# m80-v0_65.net
KiCad netlist of a schematic drawn in EAGLE
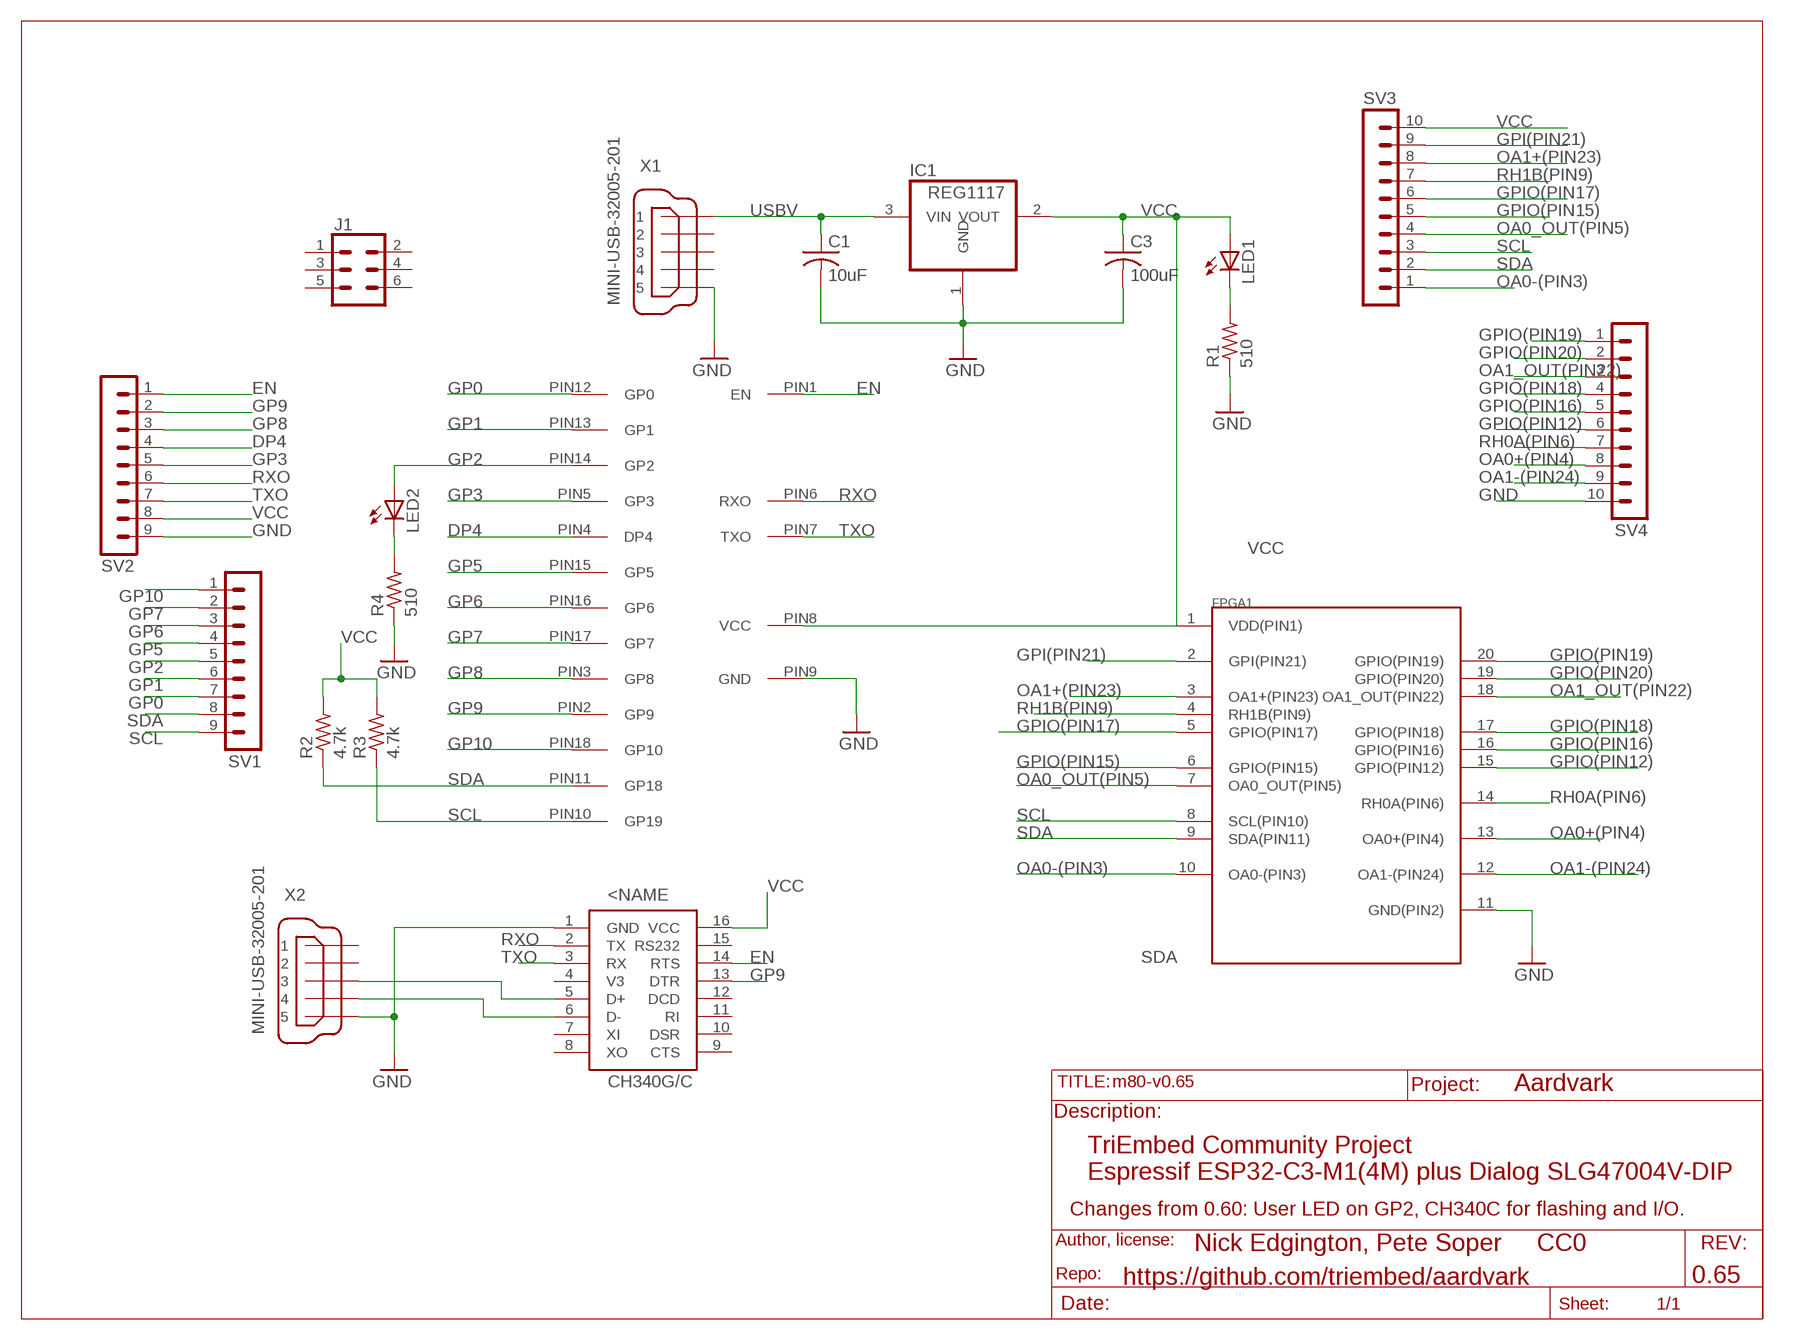
[diagram p0: schematic, sheet 1]

(export (version "E")
  (design (tool "Eeschema 10.0.6"))
  (components
    (comp (ref "C1")
      (value "10uF")
      (footprint "eagle-import:C0805")
      (libsource (lib "eagle-import") (part "C-USC0805"))
    )
    (comp (ref "C3")
      (value "100uF")
      (footprint "eagle-import:C1206")
      (libsource (lib "eagle-import") (part "C-USC1206"))
    )
    (comp (ref "FPGA1")
      (value "SLG7004V_DIP")
      (footprint "eagle-import:SLG47004V-DIP")
      (libsource (lib "eagle-import") (part "SLG7004V_DIP"))
    )
    (comp (ref "IC1")
      (value "REG1117")
      (footprint "eagle-import:SOT223")
      (libsource (lib "eagle-import") (part "REG1117"))
    )
    (comp (ref "IC2")
      (value "CH340G")
      (footprint "eagle-import:SOIC16")
      (libsource (lib "eagle-import") (part "CH340G"))
    )
    (comp (ref "J1")
      (value "CONN_03X2NO_SILK")
      (footprint "eagle-import:2X3-NS")
      (libsource (lib "eagle-import") (part "CONN_03X2NO_SILK"))
    )
    (comp (ref "LED1")
      (value "LEDCHIP-LED0805")
      (footprint "eagle-import:CHIP-LED0805")
      (libsource (lib "eagle-import") (part "LEDCHIP-LED0805"))
    )
    (comp (ref "LED2")
      (value "LEDCHIP-LED0805")
      (footprint "eagle-import:CHIP-LED0805")
      (libsource (lib "eagle-import") (part "LEDCHIP-LED0805"))
    )
    (comp (ref "R1")
      (value "510")
      (footprint "eagle-import:R0805")
      (libsource (lib "eagle-import") (part "R-US_R0805"))
    )
    (comp (ref "R2")
      (value "4.7k")
      (footprint "eagle-import:R0805")
      (libsource (lib "eagle-import") (part "R-US_R0805"))
    )
    (comp (ref "R3")
      (value "4.7k")
      (footprint "eagle-import:R0805")
      (libsource (lib "eagle-import") (part "R-US_R0805"))
    )
    (comp (ref "R4")
      (value "510")
      (footprint "eagle-import:R0805")
      (libsource (lib "eagle-import") (part "R-US_R0805"))
    )
    (comp (ref "SV1")
      (value "MA09-1")
      (footprint "eagle-import:MA09-1")
      (libsource (lib "eagle-import") (part "MA09-1"))
    )
    (comp (ref "SV2")
      (value "MA09-1")
      (footprint "eagle-import:MA09-1")
      (libsource (lib "eagle-import") (part "MA09-1"))
    )
    (comp (ref "SV3")
      (value "MA10-1")
      (footprint "eagle-import:MA10-1")
      (libsource (lib "eagle-import") (part "MA10-1"))
    )
    (comp (ref "SV4")
      (value "MA10-1")
      (footprint "eagle-import:MA10-1")
      (libsource (lib "eagle-import") (part "MA10-1"))
    )
    (comp (ref "U$2")
      (value "UNTITLED_ESP32C3")
      (footprint "eagle-import:UNTITLED_ESP32-C3-01M")
      (libsource (lib "eagle-import") (part "UNTITLED_ESP32C3"))
    )
    (comp (ref "X1")
      (value "MINI-USB-32005-201")
      (footprint "eagle-import:32005-201")
      (libsource (lib "eagle-import") (part "MINI-USB-32005-201"))
    )
    (comp (ref "X2")
      (value "MINI-USB-32005-201")
      (footprint "eagle-import:32005-201")
      (libsource (lib "eagle-import") (part "MINI-USB-32005-201"))
    )
  )
  (nets
    (net (code "1") (name "/DP4") (class "Default")
      (node (ref "SV2") (pin "4") (pinfunction "4_4") (pintype "passive"))
      (node (ref "U$2") (pin "PIN4") (pinfunction "DP4_PIN4") (pintype "bidirectional"))
    )
    (net (code "2") (name "/EN") (class "Default")
      (node (ref "IC2") (pin "14") (pinfunction "RTS_14") (pintype "bidirectional"))
      (node (ref "SV2") (pin "1") (pinfunction "1_1") (pintype "passive"))
      (node (ref "U$2") (pin "PIN1") (pinfunction "EN_PIN1") (pintype "input"))
    )
    (net (code "3") (name "/GP0") (class "Default")
      (node (ref "SV1") (pin "7") (pinfunction "7_7") (pintype "passive"))
      (node (ref "U$2") (pin "PIN12") (pinfunction "GP0_PIN12") (pintype "bidirectional"))
    )
    (net (code "4") (name "/GP1") (class "Default")
      (node (ref "SV1") (pin "6") (pinfunction "6_6") (pintype "passive"))
      (node (ref "U$2") (pin "PIN13") (pinfunction "GP1_PIN13") (pintype "bidirectional"))
    )
    (net (code "5") (name "/GP2") (class "Default")
      (node (ref "LED2") (pin "A") (pinfunction "A_A") (pintype "passive"))
      (node (ref "SV1") (pin "5") (pinfunction "5_5") (pintype "passive"))
      (node (ref "U$2") (pin "PIN14") (pinfunction "GP2_PIN14") (pintype "bidirectional"))
    )
    (net (code "6") (name "/GP3") (class "Default")
      (node (ref "SV2") (pin "5") (pinfunction "5_5") (pintype "passive"))
      (node (ref "U$2") (pin "PIN5") (pinfunction "GP3_PIN5") (pintype "bidirectional"))
    )
    (net (code "7") (name "/GP5") (class "Default")
      (node (ref "SV1") (pin "4") (pinfunction "4_4") (pintype "passive"))
      (node (ref "U$2") (pin "PIN15") (pinfunction "GP5_PIN15") (pintype "bidirectional"))
    )
    (net (code "8") (name "/GP6") (class "Default")
      (node (ref "SV1") (pin "3") (pinfunction "3_3") (pintype "passive"))
      (node (ref "U$2") (pin "PIN16") (pinfunction "GP6_PIN16") (pintype "bidirectional"))
    )
    (net (code "9") (name "/GP7") (class "Default")
      (node (ref "SV1") (pin "2") (pinfunction "2_2") (pintype "passive"))
      (node (ref "U$2") (pin "PIN17") (pinfunction "GP7_PIN17") (pintype "bidirectional"))
    )
    (net (code "10") (name "/GP8") (class "Default")
      (node (ref "SV2") (pin "3") (pinfunction "3_3") (pintype "passive"))
      (node (ref "U$2") (pin "PIN3") (pinfunction "GP8_PIN3") (pintype "bidirectional"))
    )
    (net (code "11") (name "/GP9") (class "Default")
      (node (ref "IC2") (pin "13") (pinfunction "DTR_13") (pintype "bidirectional"))
      (node (ref "SV2") (pin "2") (pinfunction "2_2") (pintype "passive"))
      (node (ref "U$2") (pin "PIN2") (pinfunction "GP9_PIN2") (pintype "bidirectional"))
    )
    (net (code "12") (name "/GP10") (class "Default")
      (node (ref "SV1") (pin "1") (pinfunction "1_1") (pintype "passive"))
      (node (ref "U$2") (pin "PIN18") (pinfunction "GP10_PIN18") (pintype "bidirectional"))
    )
    (net (code "13") (name "/GPI(PIN21)") (class "Default")
      (node (ref "FPGA1") (pin "2") (pinfunction "GPI(PIN21)_2") (pintype "input"))
      (node (ref "SV3") (pin "9") (pinfunction "9_9") (pintype "passive"))
    )
    (net (code "14") (name "/GPIO(PIN12)") (class "Default")
      (node (ref "FPGA1") (pin "15") (pinfunction "GPIO(PIN12)_15") (pintype "bidirectional"))
      (node (ref "SV4") (pin "6") (pinfunction "6_6") (pintype "passive"))
    )
    (net (code "15") (name "/GPIO(PIN15)") (class "Default")
      (node (ref "FPGA1") (pin "6") (pinfunction "GPIO(PIN15)_6") (pintype "bidirectional"))
      (node (ref "SV3") (pin "5") (pinfunction "5_5") (pintype "passive"))
    )
    (net (code "16") (name "/GPIO(PIN16)") (class "Default")
      (node (ref "FPGA1") (pin "16") (pinfunction "GPIO(PIN16)_16") (pintype "bidirectional"))
      (node (ref "SV4") (pin "5") (pinfunction "5_5") (pintype "passive"))
    )
    (net (code "17") (name "/GPIO(PIN17)") (class "Default")
      (node (ref "FPGA1") (pin "5") (pinfunction "GPIO(PIN17)_5") (pintype "bidirectional"))
      (node (ref "SV3") (pin "6") (pinfunction "6_6") (pintype "passive"))
    )
    (net (code "18") (name "/GPIO(PIN18)") (class "Default")
      (node (ref "FPGA1") (pin "17") (pinfunction "GPIO(PIN18)_17") (pintype "input"))
      (node (ref "SV4") (pin "4") (pinfunction "4_4") (pintype "passive"))
    )
    (net (code "19") (name "/GPIO(PIN19)") (class "Default")
      (node (ref "FPGA1") (pin "20") (pinfunction "GPIO(PIN19)_20") (pintype "bidirectional"))
      (node (ref "SV4") (pin "1") (pinfunction "1_1") (pintype "passive"))
    )
    (net (code "20") (name "/GPIO(PIN20)") (class "Default")
      (node (ref "FPGA1") (pin "19") (pinfunction "GPIO(PIN20)_19") (pintype "bidirectional"))
      (node (ref "SV4") (pin "2") (pinfunction "2_2") (pintype "passive"))
    )
    (net (code "21") (name "/OA0+(PIN4)") (class "Default")
      (node (ref "FPGA1") (pin "13") (pinfunction "OA0+(PIN4)_13") (pintype "bidirectional"))
      (node (ref "SV4") (pin "8") (pinfunction "8_8") (pintype "passive"))
    )
    (net (code "22") (name "/OA0-(PIN3)") (class "Default")
      (node (ref "FPGA1") (pin "10") (pinfunction "OA0-(PIN3)_10") (pintype "open_collector"))
      (node (ref "SV3") (pin "1") (pinfunction "1_1") (pintype "passive"))
    )
    (net (code "23") (name "/OA0_OUT(PIN5)") (class "Default")
      (node (ref "FPGA1") (pin "7") (pinfunction "OA0_OUT(PIN5)_7") (pintype "bidirectional"))
      (node (ref "SV3") (pin "4") (pinfunction "4_4") (pintype "passive"))
    )
    (net (code "24") (name "/OA1+(PIN23)") (class "Default")
      (node (ref "FPGA1") (pin "3") (pinfunction "OA1+(PIN23)_3") (pintype "bidirectional"))
      (node (ref "SV3") (pin "8") (pinfunction "8_8") (pintype "passive"))
    )
    (net (code "25") (name "/OA1-(PIN24)") (class "Default")
      (node (ref "FPGA1") (pin "12") (pinfunction "OA1-(PIN24)_12") (pintype "bidirectional"))
      (node (ref "SV4") (pin "9") (pinfunction "9_9") (pintype "passive"))
    )
    (net (code "26") (name "/OA1_OUT(PIN22)") (class "Default")
      (node (ref "FPGA1") (pin "18") (pinfunction "OA1_OUT(PIN22)_18") (pintype "bidirectional"))
      (node (ref "SV4") (pin "3") (pinfunction "3_3") (pintype "passive"))
    )
    (net (code "27") (name "/RH0A(PIN6)") (class "Default")
      (node (ref "FPGA1") (pin "14") (pinfunction "RH0A(PIN6)_14") (pintype "passive"))
      (node (ref "SV4") (pin "7") (pinfunction "7_7") (pintype "passive"))
    )
    (net (code "28") (name "/RH1B(PIN9)") (class "Default")
      (node (ref "FPGA1") (pin "4") (pinfunction "RH1B(PIN9)_4") (pintype "passive"))
      (node (ref "SV3") (pin "7") (pinfunction "7_7") (pintype "passive"))
    )
    (net (code "29") (name "/RXO") (class "Default")
      (node (ref "IC2") (pin "2") (pinfunction "TX_2") (pintype "bidirectional"))
      (node (ref "SV2") (pin "6") (pinfunction "6_6") (pintype "passive"))
      (node (ref "U$2") (pin "PIN6") (pinfunction "RXO_PIN6") (pintype "bidirectional"))
    )
    (net (code "30") (name "/SCL") (class "Default")
      (node (ref "FPGA1") (pin "8") (pinfunction "SCL(PIN10)_8") (pintype "bidirectional"))
      (node (ref "R3") (pin "1") (pinfunction "1_1") (pintype "passive"))
      (node (ref "SV1") (pin "9") (pinfunction "9_9") (pintype "passive"))
      (node (ref "SV3") (pin "3") (pinfunction "3_3") (pintype "passive"))
      (node (ref "U$2") (pin "PIN10") (pinfunction "GP19_PIN10") (pintype "bidirectional"))
    )
    (net (code "31") (name "/SDA") (class "Default")
      (node (ref "FPGA1") (pin "9") (pinfunction "SDA(PIN11)_9") (pintype "bidirectional"))
      (node (ref "R2") (pin "1") (pinfunction "1_1") (pintype "passive"))
      (node (ref "SV1") (pin "8") (pinfunction "8_8") (pintype "passive"))
      (node (ref "SV3") (pin "2") (pinfunction "2_2") (pintype "passive"))
      (node (ref "U$2") (pin "PIN11") (pinfunction "GP18_PIN11") (pintype "bidirectional"))
    )
    (net (code "32") (name "/TXO") (class "Default")
      (node (ref "IC2") (pin "3") (pinfunction "RX_3") (pintype "bidirectional"))
      (node (ref "SV2") (pin "7") (pinfunction "7_7") (pintype "passive"))
      (node (ref "U$2") (pin "PIN7") (pinfunction "TXO_PIN7") (pintype "bidirectional"))
    )
    (net (code "33") (name "/USBV") (class "Default")
      (node (ref "C1") (pin "1") (pinfunction "1_1") (pintype "passive"))
      (node (ref "IC1") (pin "3") (pinfunction "VIN_3") (pintype "input"))
      (node (ref "X1") (pin "1") (pinfunction "1_1") (pintype "passive"))
    )
    (net (code "34") (name "/VCC") (class "Default")
      (node (ref "C3") (pin "1") (pinfunction "1_1") (pintype "passive"))
      (node (ref "FPGA1") (pin "1") (pinfunction "VDD(PIN1)_1") (pintype "power_in"))
      (node (ref "IC1") (pin "2") (pinfunction "VOUT_2") (pintype "output"))
      (node (ref "IC2") (pin "16") (pinfunction "VCC_16") (pintype "power_in"))
      (node (ref "LED1") (pin "A") (pinfunction "A_A") (pintype "passive"))
      (node (ref "R2") (pin "2") (pinfunction "2_2") (pintype "passive"))
      (node (ref "R3") (pin "2") (pinfunction "2_2") (pintype "passive"))
      (node (ref "SV2") (pin "8") (pinfunction "8_8") (pintype "passive"))
      (node (ref "SV3") (pin "10") (pinfunction "10_10") (pintype "passive"))
      (node (ref "U$2") (pin "PIN8") (pinfunction "VCC_PIN8") (pintype "power_in"))
    )
    (net (code "35") (name "GND") (class "Default")
      (node (ref "C1") (pin "2") (pinfunction "2_2") (pintype "passive"))
      (node (ref "C3") (pin "2") (pinfunction "2_2") (pintype "passive"))
      (node (ref "FPGA1") (pin "11") (pinfunction "GND(PIN2)_11") (pintype "power_in"))
      (node (ref "IC1") (pin "1") (pinfunction "GND_1") (pintype "power_in"))
      (node (ref "IC2") (pin "1") (pinfunction "GND_1") (pintype "power_in"))
      (node (ref "R1") (pin "1") (pinfunction "1_1") (pintype "passive"))
      (node (ref "R4") (pin "1") (pinfunction "1_1") (pintype "passive"))
      (node (ref "SV2") (pin "9") (pinfunction "9_9") (pintype "passive"))
      (node (ref "SV4") (pin "10") (pinfunction "10_10") (pintype "passive"))
      (node (ref "U$2") (pin "PIN9") (pinfunction "GND_PIN9") (pintype "power_in"))
      (node (ref "X1") (pin "5") (pinfunction "5_5") (pintype "passive"))
      (node (ref "X2") (pin "5") (pinfunction "5_5") (pintype "passive"))
    )
    (net (code "36") (name "Net-(IC2-D+)") (class "Default")
      (node (ref "IC2") (pin "5") (pinfunction "D+_5") (pintype "bidirectional"))
      (node (ref "X2") (pin "3") (pinfunction "3_3") (pintype "passive"))
    )
    (net (code "37") (name "Net-(IC2-D-)") (class "Default")
      (node (ref "IC2") (pin "6") (pinfunction "D-_6") (pintype "bidirectional"))
      (node (ref "X2") (pin "4") (pinfunction "4_4") (pintype "passive"))
    )
    (net (code "38") (name "Net-(LED1-PadC)") (class "Default")
      (node (ref "LED1") (pin "C") (pinfunction "C_C") (pintype "passive"))
      (node (ref "R1") (pin "2") (pinfunction "2_2") (pintype "passive"))
    )
    (net (code "39") (name "Net-(LED2-PadC)") (class "Default")
      (node (ref "LED2") (pin "C") (pinfunction "C_C") (pintype "passive"))
      (node (ref "R4") (pin "2") (pinfunction "2_2") (pintype "passive"))
    )
    (net (code "40") (name "unconnected-(IC2-CTS-Pad9)") (class "Default")
      (node (ref "IC2") (pin "9") (pinfunction "CTS_9") (pintype "bidirectional"))
    )
    (net (code "41") (name "unconnected-(IC2-DCD-Pad12)") (class "Default")
      (node (ref "IC2") (pin "12") (pinfunction "DCD_12") (pintype "bidirectional"))
    )
    (net (code "42") (name "unconnected-(IC2-DSR-Pad10)") (class "Default")
      (node (ref "IC2") (pin "10") (pinfunction "DSR_10") (pintype "bidirectional"))
    )
    (net (code "43") (name "unconnected-(IC2-RI-Pad11)") (class "Default")
      (node (ref "IC2") (pin "11") (pinfunction "RI_11") (pintype "bidirectional"))
    )
    (net (code "44") (name "unconnected-(IC2-RS232-Pad15)") (class "Default")
      (node (ref "IC2") (pin "15") (pinfunction "RS232_15") (pintype "bidirectional"))
    )
    (net (code "45") (name "unconnected-(IC2-V3-Pad4)") (class "Default")
      (node (ref "IC2") (pin "4") (pinfunction "V3_4") (pintype "bidirectional"))
    )
    (net (code "46") (name "unconnected-(IC2-XI-Pad7)") (class "Default")
      (node (ref "IC2") (pin "7") (pinfunction "XI_7") (pintype "bidirectional"))
    )
    (net (code "47") (name "unconnected-(IC2-XO-Pad8)") (class "Default")
      (node (ref "IC2") (pin "8") (pinfunction "XO_8") (pintype "bidirectional"))
    )
    (net (code "48") (name "unconnected-(J1-Pad1)") (class "Default")
      (node (ref "J1") (pin "1") (pinfunction "1_1") (pintype "bidirectional"))
    )
    (net (code "49") (name "unconnected-(J1-Pad2)") (class "Default")
      (node (ref "J1") (pin "2") (pinfunction "2_2") (pintype "bidirectional"))
    )
    (net (code "50") (name "unconnected-(J1-Pad3)") (class "Default")
      (node (ref "J1") (pin "3") (pinfunction "3_3") (pintype "bidirectional"))
    )
    (net (code "51") (name "unconnected-(J1-Pad4)") (class "Default")
      (node (ref "J1") (pin "4") (pinfunction "4_4") (pintype "bidirectional"))
    )
    (net (code "52") (name "unconnected-(J1-Pad5)") (class "Default")
      (node (ref "J1") (pin "5") (pinfunction "5_5") (pintype "bidirectional"))
    )
    (net (code "53") (name "unconnected-(J1-Pad6)") (class "Default")
      (node (ref "J1") (pin "6") (pinfunction "6_6") (pintype "bidirectional"))
    )
    (net (code "54") (name "unconnected-(X1-Pad2)") (class "Default")
      (node (ref "X1") (pin "2") (pinfunction "2_2") (pintype "passive"))
    )
    (net (code "55") (name "unconnected-(X1-Pad3)") (class "Default")
      (node (ref "X1") (pin "3") (pinfunction "3_3") (pintype "passive"))
    )
    (net (code "56") (name "unconnected-(X1-Pad4)") (class "Default")
      (node (ref "X1") (pin "4") (pinfunction "4_4") (pintype "passive"))
    )
    (net (code "57") (name "unconnected-(X2-Pad1)") (class "Default")
      (node (ref "X2") (pin "1") (pinfunction "1_1") (pintype "passive"))
    )
    (net (code "58") (name "unconnected-(X2-Pad2)") (class "Default")
      (node (ref "X2") (pin "2") (pinfunction "2_2") (pintype "passive"))
    )
  )
)
